# HV_DRV_PA15FLA.net
KiCad netlist of a schematic drawn in Altium Designer
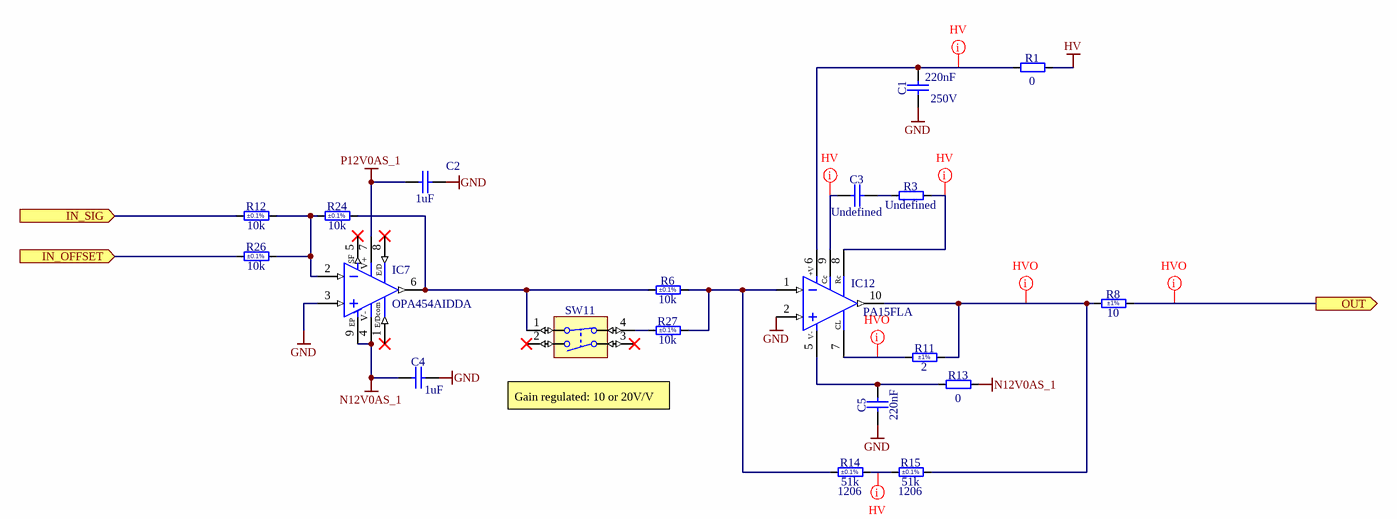
[diagram p0: HV_DRV_PA15FLA.SchDoc]

(export (version "E")
  (design (tool "Eeschema 10.0.6"))
  (components
    (comp (ref "C1")
      (value "220nF")
      (footprint "CAPC4532X165N")
      (description "Non-polarised capacitor")
      (fields
        (field (name "PART NUMBER") "CC1812_220NF_250V_10%_X7R_FT-CAP")
        (field (name "VOLTAGE") "250V")
        (field (name "TOLERANCE") "±10%")
        (field (name "AUTHOR") "CERN DEM JLC")
      )
      (libsource (lib "Capacitors") (part "Capacitor - non polarized"))
    )
    (comp (ref "C2")
      (value "1uF")
      (footprint "CAPC1608X87N")
      (description "Non-polarised capacitor")
      (fields
        (field (name "PART NUMBER") "CC0603_1UF_50V_10%_X5R")
        (field (name "VOLTAGE") "50V")
        (field (name "AUTHOR") "CERN DEM JMW")
      )
      (libsource (lib "Capacitors") (part "Capacitor - non polarized"))
    )
    (comp (ref "C3")
      (value "Undefined")
      (footprint "CAPC3216X140N")
      (description "Non-polarised capacitor")
      (fields (field (name "PART NUMBER") "CC1206_NO-VALUE") (field (name "AUTHOR") "CERN DEM JLC"))
      (libsource (lib "Capacitors") (part "Capacitor - non polarized"))
    )
    (comp (ref "C4")
      (value "1uF")
      (footprint "CAPC1608X87N")
      (description "Non-polarised capacitor")
      (fields
        (field (name "PART NUMBER") "CC0603_1UF_50V_10%_X5R")
        (field (name "VOLTAGE") "50V")
        (field (name "AUTHOR") "CERN DEM JMW")
      )
      (libsource (lib "Capacitors") (part "Capacitor - non polarized"))
    )
    (comp (ref "C5")
      (value "220nF")
      (footprint "CAPC1608X87N")
      (description "Non-polarised capacitor")
      (fields
        (field (name "PART NUMBER") "CC0603_220NF_25V_10%_X7R")
        (field (name "VOLTAGE") "25V")
        (field (name "AUTHOR") "CERN DEM JLC")
      )
      (libsource (lib "Capacitors") (part "Capacitor - non polarized"))
    )
    (comp (ref "IC7")
      (value "OPA454AIDDA")
      (footprint "SOIC127P600X170-9N-R249X300")
      (description "High-Voltage (100V), High-Current (50mA) Operational Amplifier, G=1 Stable")
      (fields (field (name "MANUFACTURER") "TEXAS INSTRUMENTS") (field (name "AUTHOR") "CERN DEM JLC"))
      (libsource (lib "ICs And Semiconductors") (part "OPA454"))
    )
    (comp (ref "IC12")
      (value "PA15FLA")
      (footprint "APEX_PA15FL_v")
      (description "High Voltage Power Operational Amplifier")
      (fields
        (field (name "PART NUMBER") "PA15FLA_v")
        (field (name "MANUFACTURER") "APEX MICROTECHNOLOGY")
        (field (name "AUTHOR") "CERN DEM BC")
      )
      (libsource (lib "ICs And Semiconductors") (part "PA15"))
    )
    (comp (ref "R1")
      (value "0")
      (footprint "RESC1608X55N")
      (description "Resistor")
      (fields
        (field (name "PART NUMBER") "R0603_0R_JUMPER")
        (field (name "MANUFACTURER") "GENERIC")
        (field (name "AUTHOR") "CERN DEM JLC")
      )
      (libsource (lib "Resistors") (part "Resistor"))
    )
    (comp (ref "R3")
      (value "Undefined")
      (footprint "RESC3216X65N")
      (description "Resistor")
      (fields (field (name "PART NUMBER") "R1206_NO-VALUE") (field (name "AUTHOR") "CERN DEM JLC"))
      (libsource (lib "Resistors") (part "Resistor"))
    )
    (comp (ref "R6")
      (value "10k")
      (footprint "RESC1608X64N")
      (description "Resistor - 0.1%")
      (fields
        (field (name "TOLERANCE") "±0.1%")
        (field (name "PART NUMBER") "R0603_10K_0.1%_0.1W_25PPM")
        (field (name "POWER") "0.1W")
        (field (name "AUTHOR") "CERN DEM JMW")
      )
      (libsource (lib "Resistors") (part "Resistor - 0.1%"))
    )
    (comp (ref "R8")
      (value "10")
      (footprint "RESC3216X65N")
      (description "Resistor - 1%")
      (fields
        (field (name "TOLERANCE") "±1%")
        (field (name "PART NUMBER") "R1206_10R_1%_0.25W_200PPM")
        (field (name "POWER") "0.25W")
        (field (name "AUTHOR") "CERN DEM JLC")
      )
      (libsource (lib "Resistors") (part "Resistor - 1%"))
    )
    (comp (ref "R11")
      (value "2")
      (footprint "RESC1608X55N")
      (description "Resistor - 1%")
      (fields
        (field (name "TOLERANCE") "±1%")
        (field (name "PART NUMBER") "R0603_2R_1%_0.1W_200PPM")
        (field (name "POWER") "0.1W")
        (field (name "AUTHOR") "CERN DEM JLC")
      )
      (libsource (lib "Resistors") (part "Resistor - 1%"))
    )
    (comp (ref "R12")
      (value "10k")
      (footprint "RESC1608X55N")
      (description "Resistor - 0.1%")
      (fields
        (field (name "TOLERANCE") "±0.1%")
        (field (name "PART NUMBER") "R0603_10K_0.1%_0.063W_10PPM")
        (field (name "POWER") "0.063W")
        (field (name "AUTHOR") "CERN DEM JLC")
      )
      (libsource (lib "Resistors") (part "Resistor - 0.1%"))
    )
    (comp (ref "R13")
      (value "0")
      (footprint "RESC1608X55N")
      (description "Resistor")
      (fields
        (field (name "PART NUMBER") "R0603_0R_JUMPER")
        (field (name "MANUFACTURER") "GENERIC")
        (field (name "AUTHOR") "CERN DEM JLC")
      )
      (libsource (lib "Resistors") (part "Resistor"))
    )
    (comp (ref "R14")
      (value "51k")
      (footprint "RESC3216X65N")
      (description "Resistor - 0.1%")
      (fields
        (field (name "TOLERANCE") "±0.1%")
        (field (name "PART NUMBER") "R1206_51K_0.1%_0.25W_25PPM")
        (field (name "POWER") "0.25W")
        (field (name "CASE") "1206")
        (field (name "AUTHOR") "CERN DEM JLC")
      )
      (libsource (lib "Resistors") (part "Resistor - 0.1%"))
    )
    (comp (ref "R15")
      (value "51k")
      (footprint "RESC3216X65N")
      (description "Resistor - 0.1%")
      (fields
        (field (name "TOLERANCE") "±0.1%")
        (field (name "PART NUMBER") "R1206_51K_0.1%_0.25W_25PPM")
        (field (name "POWER") "0.25W")
        (field (name "CASE") "1206")
        (field (name "AUTHOR") "CERN DEM JLC")
      )
      (libsource (lib "Resistors") (part "Resistor - 0.1%"))
    )
    (comp (ref "R24")
      (value "10k")
      (footprint "RESC1608X55N")
      (description "Resistor - 0.1%")
      (fields
        (field (name "TOLERANCE") "±0.1%")
        (field (name "PART NUMBER") "R0603_10K_0.1%_0.063W_10PPM")
        (field (name "POWER") "0.063W")
        (field (name "AUTHOR") "CERN DEM JLC")
      )
      (libsource (lib "Resistors") (part "Resistor - 0.1%"))
    )
    (comp (ref "R26")
      (value "10k")
      (footprint "RESC1608X55N")
      (description "Resistor - 0.1%")
      (fields
        (field (name "TOLERANCE") "±0.1%")
        (field (name "PART NUMBER") "R0603_10K_0.1%_0.063W_10PPM")
        (field (name "POWER") "0.063W")
        (field (name "AUTHOR") "CERN DEM JLC")
      )
      (libsource (lib "Resistors") (part "Resistor - 0.1%"))
    )
    (comp (ref "R27")
      (value "10k")
      (footprint "RESC1608X64N")
      (description "Resistor - 0.1%")
      (fields
        (field (name "TOLERANCE") "±0.1%")
        (field (name "PART NUMBER") "R0603_10K_0.1%_0.1W_25PPM")
        (field (name "POWER") "0.1W")
        (field (name "AUTHOR") "CERN DEM JMW")
      )
      (libsource (lib "Resistors") (part "Resistor - 0.1%"))
    )
    (comp (ref "SW11")
      (value "Switch")
      (footprint "SW_CTS_204-121ST")
      (description "2x SPST DIP Switch 1NO + 1NF")
      (fields
        (field (name "PART NUMBER") "SW_CTS_204-121ST")
        (field (name "MANUFACTURER") "CTS")
        (field (name "AUTHOR") "CERN DEM JLC")
      )
      (libsource (lib "Eletro-mechanical") (part "SW_CTS_204-121ST"))
    )
  )
  (nets
    (net (code "1") (name "/IN_OFFSET") (class "Default")
      (node (ref "R26") (pin "1") (pinfunction "1_1") (pintype "passive"))
    )
    (net (code "2") (name "/IN_SIG") (class "Default")
      (node (ref "R12") (pin "1") (pinfunction "1_1") (pintype "passive"))
    )
    (net (code "3") (name "/OUT") (class "Default")
      (node (ref "R8") (pin "2") (pinfunction "2_2") (pintype "passive"))
    )
    (net (code "4") (name "GND") (class "Default")
      (node (ref "C1") (pin "1") (pinfunction "1_1") (pintype "passive"))
      (node (ref "C2") (pin "2") (pinfunction "2_2") (pintype "passive"))
      (node (ref "C4") (pin "2") (pinfunction "2_2") (pintype "passive"))
      (node (ref "C5") (pin "1") (pinfunction "1_1") (pintype "passive"))
      (node (ref "IC12") (pin "2") (pinfunction "IN+_2") (pintype "input"))
      (node (ref "IC7") (pin "3") (pinfunction "IN+_3") (pintype "input"))
    )
    (net (code "5") (name "HV") (class "Default")
      (node (ref "R1") (pin "2") (pinfunction "2_2") (pintype "passive"))
    )
    (net (code "6") (name "N12V0AS_1") (class "Default")
      (node (ref "C4") (pin "1") (pinfunction "1_1") (pintype "passive"))
      (node (ref "IC7") (pin "4") (pinfunction "V-_4") (pintype "power_in"))
      (node (ref "IC7") (pin "9") (pinfunction "Exposed_Pad_9") (pintype "power_in"))
      (node (ref "R13") (pin "2") (pinfunction "2_2") (pintype "passive"))
    )
    (net (code "7") (name "Net-(C3-Pad2)") (class "Default")
      (node (ref "C3") (pin "2") (pinfunction "2_2") (pintype "passive"))
      (node (ref "R3") (pin "1") (pinfunction "1_1") (pintype "passive"))
    )
    (net (code "8") (name "Net-(IC7-IN-)") (class "Default")
      (node (ref "IC7") (pin "2") (pinfunction "IN-_2") (pintype "input"))
      (node (ref "R12") (pin "2") (pinfunction "2_2") (pintype "passive"))
      (node (ref "R24") (pin "1") (pinfunction "1_1") (pintype "passive"))
      (node (ref "R26") (pin "2") (pinfunction "2_2") (pintype "passive"))
    )
    (net (code "9") (name "Net-(IC7-OUT)") (class "Default")
      (node (ref "IC7") (pin "6") (pinfunction "OUT_6") (pintype "output"))
      (node (ref "R24") (pin "2") (pinfunction "2_2") (pintype "passive"))
      (node (ref "R6") (pin "1") (pinfunction "1_1") (pintype "passive"))
      (node (ref "SW11") (pin "1") (pinfunction "1_1") (pintype "bidirectional"))
    )
    (net (code "10") (name "Net-(IC12-+Vs)") (class "Default")
      (node (ref "C1") (pin "2") (pinfunction "2_2") (pintype "passive"))
      (node (ref "IC12") (pin "6") (pinfunction "+Vs_6") (pintype "power_in"))
      (node (ref "R1") (pin "1") (pinfunction "1_1") (pintype "passive"))
    )
    (net (code "11") (name "Net-(IC12--Vs)") (class "Default")
      (node (ref "C5") (pin "2") (pinfunction "2_2") (pintype "passive"))
      (node (ref "IC12") (pin "5") (pinfunction "-Vs_5") (pintype "power_in"))
      (node (ref "R13") (pin "1") (pinfunction "1_1") (pintype "passive"))
    )
    (net (code "12") (name "Net-(IC12-CL)") (class "Default")
      (node (ref "IC12") (pin "7") (pinfunction "CL_7") (pintype "passive"))
      (node (ref "R11") (pin "1") (pinfunction "1_1") (pintype "passive"))
    )
    (net (code "13") (name "Net-(IC12-Cc)") (class "Default")
      (node (ref "C3") (pin "1") (pinfunction "1_1") (pintype "passive"))
      (node (ref "IC12") (pin "9") (pinfunction "Cc_9") (pintype "passive"))
    )
    (net (code "14") (name "Net-(IC12-Cc2)") (class "Default")
      (node (ref "IC12") (pin "8") (pinfunction "Cc2_8") (pintype "passive"))
      (node (ref "R3") (pin "2") (pinfunction "2_2") (pintype "passive"))
    )
    (net (code "15") (name "Net-(IC12-IN-)") (class "Default")
      (node (ref "IC12") (pin "1") (pinfunction "IN-_1") (pintype "input"))
      (node (ref "R14") (pin "1") (pinfunction "1_1") (pintype "passive"))
      (node (ref "R27") (pin "2") (pinfunction "2_2") (pintype "passive"))
      (node (ref "R6") (pin "2") (pinfunction "2_2") (pintype "passive"))
    )
    (net (code "16") (name "Net-(IC12-OUT)") (class "Default")
      (node (ref "IC12") (pin "10") (pinfunction "OUT_10") (pintype "output"))
      (node (ref "R11") (pin "2") (pinfunction "2_2") (pintype "passive"))
      (node (ref "R15") (pin "2") (pinfunction "2_2") (pintype "passive"))
      (node (ref "R8") (pin "1") (pinfunction "1_1") (pintype "passive"))
    )
    (net (code "17") (name "Net-(R14-Pad2)") (class "Default")
      (node (ref "R14") (pin "2") (pinfunction "2_2") (pintype "passive"))
      (node (ref "R15") (pin "1") (pinfunction "1_1") (pintype "passive"))
    )
    (net (code "18") (name "Net-(R27-Pad1)") (class "Default")
      (node (ref "R27") (pin "1") (pinfunction "1_1") (pintype "passive"))
      (node (ref "SW11") (pin "4") (pinfunction "4_4") (pintype "bidirectional"))
    )
    (net (code "19") (name "P12V0AS_1") (class "Default")
      (node (ref "C2") (pin "1") (pinfunction "1_1") (pintype "passive"))
      (node (ref "IC7") (pin "7") (pinfunction "V+_7") (pintype "power_in"))
    )
    (net (code "20") (name "unconnected-(IC7-E{slash}B-Pad8)") (class "Default")
      (node (ref "IC7") (pin "8") (pinfunction "E/B_8") (pintype "input+no_connect"))
    )
    (net (code "21") (name "unconnected-(IC7-E{slash}Dcommon-Pad1)") (class "Default")
      (node (ref "IC7") (pin "1") (pinfunction "E/Dcommon_1") (pintype "input+no_connect"))
    )
    (net (code "22") (name "unconnected-(IC7-Status_Flag-Pad5)") (class "Default")
      (node (ref "IC7") (pin "5") (pinfunction "Status_Flag_5") (pintype "output+no_connect"))
    )
    (net (code "23") (name "unconnected-(SW11-Pad2)") (class "Default")
      (node (ref "SW11") (pin "2") (pinfunction "2_2") (pintype "bidirectional+no_connect"))
    )
    (net (code "24") (name "unconnected-(SW11-Pad3)") (class "Default")
      (node (ref "SW11") (pin "3") (pinfunction "3_3") (pintype "bidirectional+no_connect"))
    )
  )
)
